# DIP_VERSION.net
KiCad netlist of a schematic drawn in EAGLE
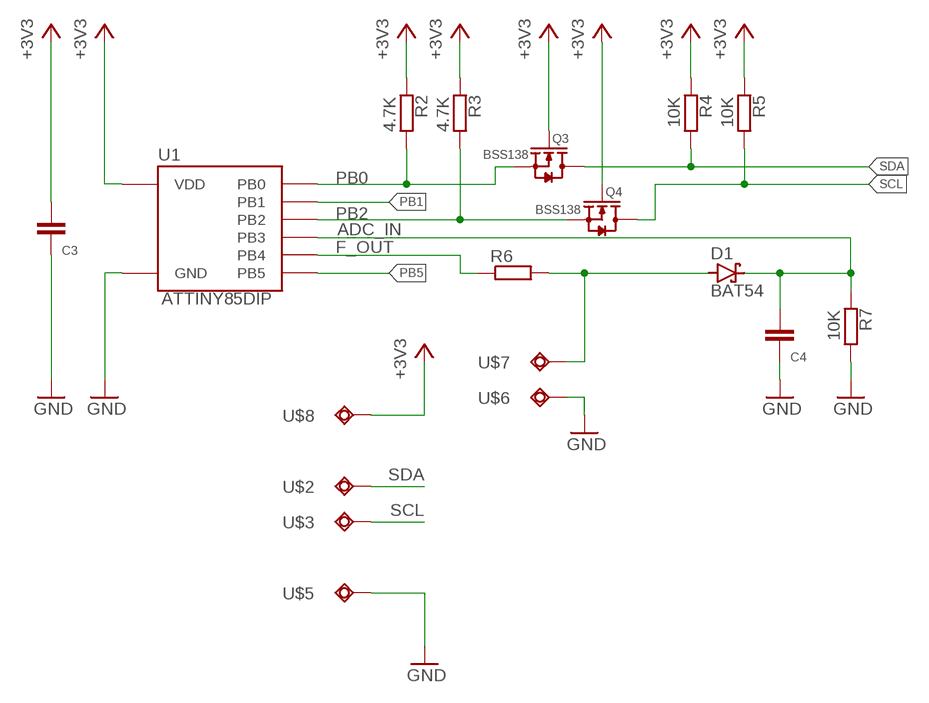
[diagram p0: schematic, sheet 1]

(export (version "E")
  (design (tool "Eeschema 10.0.6"))
  (components
    (comp (ref "C3")
      (value "100nF 6.3V")
      (footprint "eagle-import:SMD_0805")
      (libsource (lib "eagle-import") (part "CAP_CERAMIC_0805"))
    )
    (comp (ref "C4")
      (value "10UF 6.3V")
      (footprint "eagle-import:SMD_0805")
      (libsource (lib "eagle-import") (part "CAP_CERAMIC_0805"))
    )
    (comp (ref "D1")
      (value "BAT54")
      (footprint "eagle-import:SOT23")
      (libsource (lib "eagle-import") (part "BAT54"))
    )
    (comp (ref "Q3")
      (value "BSS138")
      (footprint "eagle-import:SOT-23")
      (fields (field (name "MPN") "BSS138W-7-F"))
      (libsource (lib "eagle-import") (part "SMD-MOSFET-N-CH-50V-200MA-BSS138W-7-F(SOT-23)"))
    )
    (comp (ref "Q4")
      (value "BSS138")
      (footprint "eagle-import:SOT-23")
      (fields (field (name "MPN") "BSS138W-7-F"))
      (libsource (lib "eagle-import") (part "SMD-MOSFET-N-CH-50V-200MA-BSS138W-7-F(SOT-23)"))
    )
    (comp (ref "R2")
      (value "4.7K")
      (footprint "eagle-import:SMD_0805")
      (libsource (lib "eagle-import") (part "RESISTOR_0805"))
    )
    (comp (ref "R3")
      (value "4.7K")
      (footprint "eagle-import:SMD_0805")
      (libsource (lib "eagle-import") (part "RESISTOR_0805"))
    )
    (comp (ref "R4")
      (value "10K")
      (footprint "eagle-import:SMD_0805")
      (libsource (lib "eagle-import") (part "RESISTOR_0805"))
    )
    (comp (ref "R5")
      (value "10K")
      (footprint "eagle-import:SMD_0805")
      (libsource (lib "eagle-import") (part "RESISTOR_0805"))
    )
    (comp (ref "R6")
      (value "6.25")
      (footprint "eagle-import:SMD_0805")
      (libsource (lib "eagle-import") (part "RESISTOR_0805"))
    )
    (comp (ref "R7")
      (value "10K")
      (footprint "eagle-import:SMD_0805")
      (libsource (lib "eagle-import") (part "RESISTOR_0805"))
    )
    (comp (ref "U$2")
      (value "PAD3.0X5.0")
      (footprint "eagle-import:PAD3X5")
      (libsource (lib "eagle-import") (part "PAD3.0X5.0"))
    )
    (comp (ref "U$3")
      (value "PAD3.0X5.0")
      (footprint "eagle-import:PAD3X5")
      (libsource (lib "eagle-import") (part "PAD3.0X5.0"))
    )
    (comp (ref "U$5")
      (value "PAD3.0X5.0")
      (footprint "eagle-import:PAD3X5")
      (libsource (lib "eagle-import") (part "PAD3.0X5.0"))
    )
    (comp (ref "U$6")
      (value "PAD3.0X5.0")
      (footprint "eagle-import:PAD3X5")
      (libsource (lib "eagle-import") (part "PAD3.0X5.0"))
    )
    (comp (ref "U$7")
      (value "PAD3.0X5.0")
      (footprint "eagle-import:PAD3X5")
      (libsource (lib "eagle-import") (part "PAD3.0X5.0"))
    )
    (comp (ref "U$8")
      (value "PAD3.0X5.0")
      (footprint "eagle-import:PAD3X5")
      (libsource (lib "eagle-import") (part "PAD3.0X5.0"))
    )
    (comp (ref "U1")
      (value "ATTINY85DIP")
      (footprint "eagle-import:DIP8")
      (libsource (lib "eagle-import") (part "ATTINY85DIP"))
    )
  )
  (nets
    (net (code "1") (name "+3V3") (class "Default")
      (node (ref "C3") (pin "2") (pinfunction "2_2") (pintype "passive"))
      (node (ref "Q3") (pin "1") (pinfunction "G_1") (pintype "passive"))
      (node (ref "Q4") (pin "1") (pinfunction "G_1") (pintype "passive"))
      (node (ref "R2") (pin "1") (pinfunction "1_1") (pintype "passive"))
      (node (ref "R3") (pin "1") (pinfunction "1_1") (pintype "passive"))
      (node (ref "R4") (pin "1") (pinfunction "1_1") (pintype "passive"))
      (node (ref "R5") (pin "1") (pinfunction "1_1") (pintype "passive"))
      (node (ref "U$8") (pin "P$1") (pinfunction "P$1_P$1") (pintype "bidirectional"))
      (node (ref "U1") (pin "8") (pinfunction "VDD_8") (pintype "bidirectional"))
    )
    (net (code "2") (name "/ADC_IN") (class "Default")
      (node (ref "C4") (pin "2") (pinfunction "2_2") (pintype "passive"))
      (node (ref "D1") (pin "3") (pinfunction "C_3") (pintype "passive"))
      (node (ref "R7") (pin "1") (pinfunction "1_1") (pintype "passive"))
      (node (ref "U1") (pin "2") (pinfunction "PB3_2") (pintype "bidirectional"))
    )
    (net (code "3") (name "/F_OUT") (class "Default")
      (node (ref "R6") (pin "1") (pinfunction "1_1") (pintype "passive"))
      (node (ref "U1") (pin "3") (pinfunction "PB4_3") (pintype "bidirectional"))
    )
    (net (code "4") (name "/PB0") (class "Default")
      (node (ref "Q3") (pin "2") (pinfunction "S_2") (pintype "passive"))
      (node (ref "R2") (pin "2") (pinfunction "2_2") (pintype "passive"))
      (node (ref "U1") (pin "5") (pinfunction "PB0_5") (pintype "bidirectional"))
    )
    (net (code "5") (name "/PB2") (class "Default")
      (node (ref "Q4") (pin "2") (pinfunction "S_2") (pintype "passive"))
      (node (ref "R3") (pin "2") (pinfunction "2_2") (pintype "passive"))
      (node (ref "U1") (pin "7") (pinfunction "PB2_7") (pintype "bidirectional"))
    )
    (net (code "6") (name "GND") (class "Default")
      (node (ref "C3") (pin "1") (pinfunction "1_1") (pintype "passive"))
      (node (ref "C4") (pin "1") (pinfunction "1_1") (pintype "passive"))
      (node (ref "R7") (pin "2") (pinfunction "2_2") (pintype "passive"))
      (node (ref "U$5") (pin "P$1") (pinfunction "P$1_P$1") (pintype "bidirectional"))
      (node (ref "U$6") (pin "P$1") (pinfunction "P$1_P$1") (pintype "bidirectional"))
      (node (ref "U1") (pin "4") (pinfunction "GND_4") (pintype "bidirectional"))
    )
    (net (code "7") (name "Net-(D1-A)") (class "Default")
      (node (ref "D1") (pin "1") (pinfunction "A_1") (pintype "passive"))
      (node (ref "R6") (pin "2") (pinfunction "2_2") (pintype "passive"))
      (node (ref "U$7") (pin "P$1") (pinfunction "P$1_P$1") (pintype "bidirectional"))
    )
    (net (code "8") (name "PB1") (class "Default")
      (node (ref "U1") (pin "6") (pinfunction "PB1_6") (pintype "bidirectional"))
    )
    (net (code "9") (name "PB5") (class "Default")
      (node (ref "U1") (pin "1") (pinfunction "PB5_1") (pintype "bidirectional"))
    )
    (net (code "10") (name "SCL") (class "Default")
      (node (ref "Q4") (pin "3") (pinfunction "D_3") (pintype "passive"))
      (node (ref "R5") (pin "2") (pinfunction "2_2") (pintype "passive"))
      (node (ref "U$3") (pin "P$1") (pinfunction "P$1_P$1") (pintype "bidirectional"))
    )
    (net (code "11") (name "SDA") (class "Default")
      (node (ref "Q3") (pin "3") (pinfunction "D_3") (pintype "passive"))
      (node (ref "R4") (pin "2") (pinfunction "2_2") (pintype "passive"))
      (node (ref "U$2") (pin "P$1") (pinfunction "P$1_P$1") (pintype "bidirectional"))
    )
  )
)
